# beerSch00.net
KiCad netlist of a schematic drawn in EAGLE
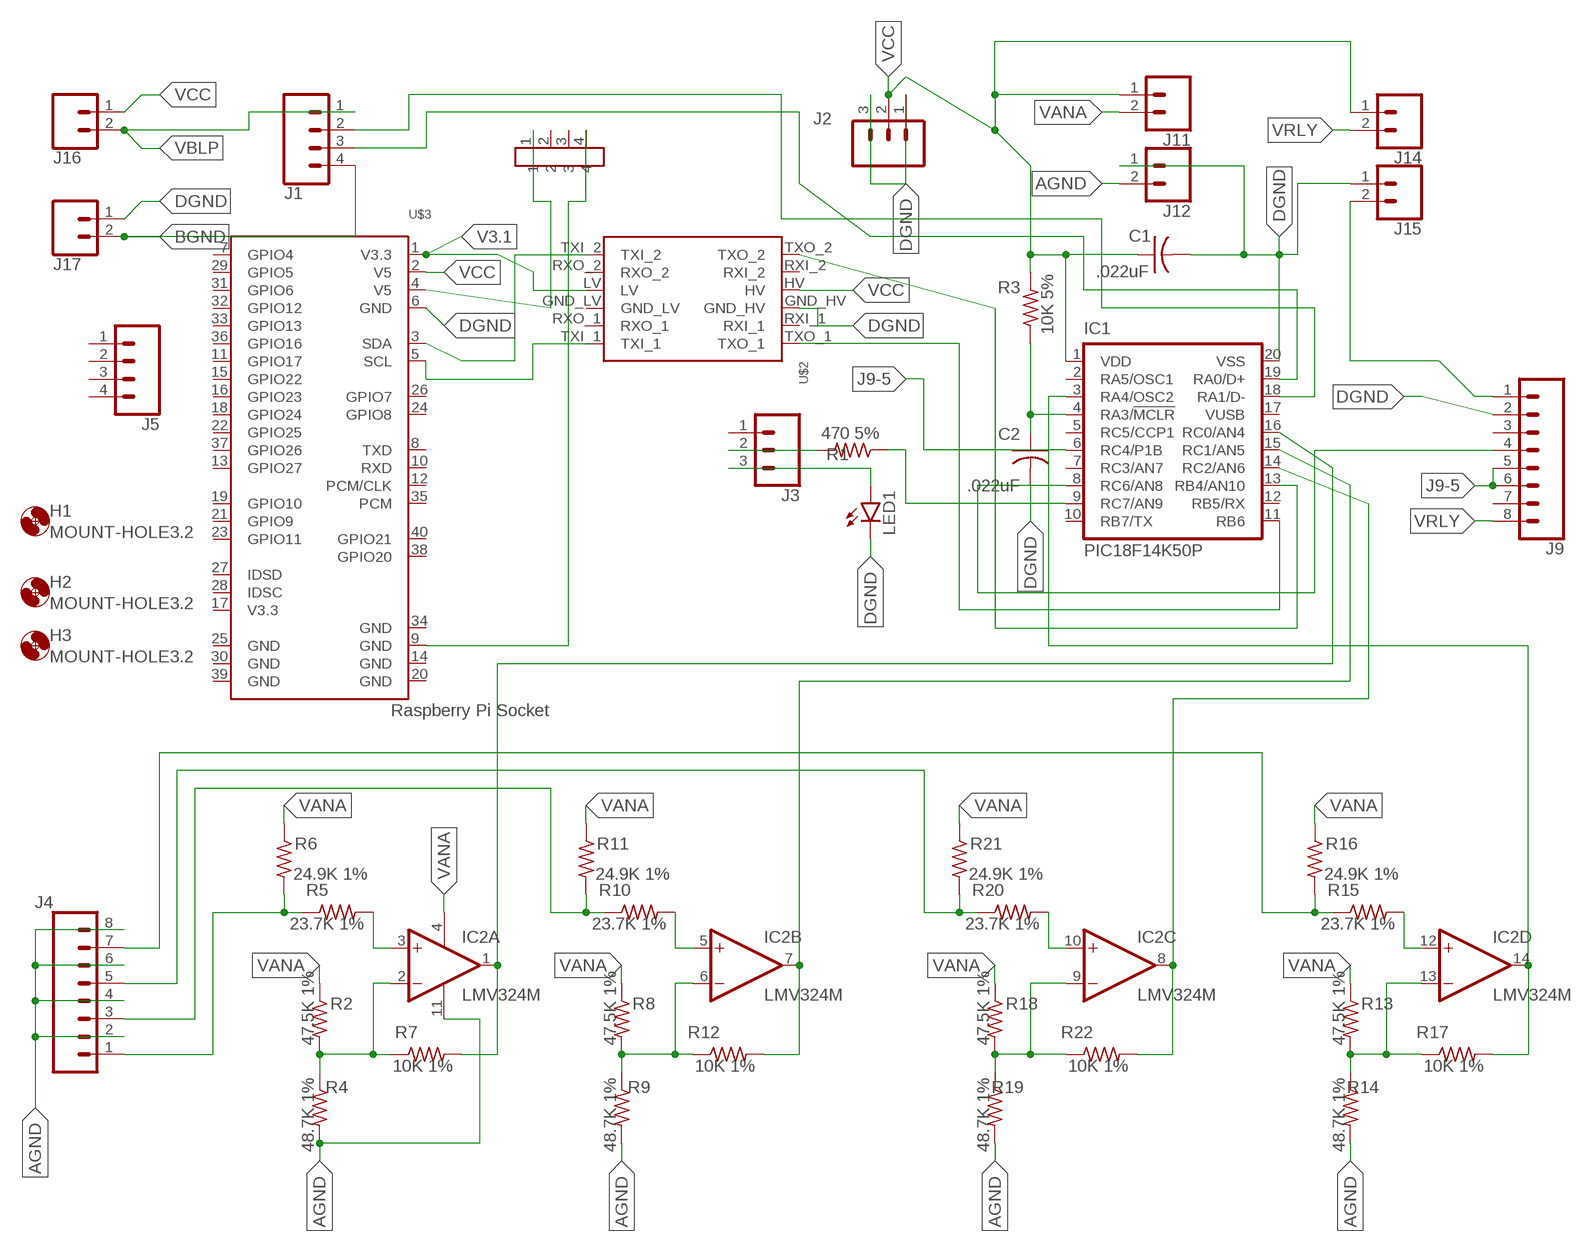
[diagram p0: schematic, sheet 1]

(export (version "E")
  (design (tool "Eeschema 10.0.6"))
  (components
    (comp (ref "C1")
      (value ".022uF")
      (footprint "eagle-import:C0805")
      (libsource (lib "eagle-import") (part "C-USC0805"))
    )
    (comp (ref "C2")
      (value ".022uF")
      (footprint "eagle-import:C0805")
      (libsource (lib "eagle-import") (part "C-USC0805"))
    )
    (comp (ref "H1")
      (value "MOUNT-HOLE3.2")
      (footprint "eagle-import:3,2")
      (libsource (lib "eagle-import") (part "MOUNT-HOLE3.2"))
    )
    (comp (ref "H2")
      (value "MOUNT-HOLE3.2")
      (footprint "eagle-import:3,2")
      (libsource (lib "eagle-import") (part "MOUNT-HOLE3.2"))
    )
    (comp (ref "H3")
      (value "MOUNT-HOLE3.2")
      (footprint "eagle-import:3,2")
      (libsource (lib "eagle-import") (part "MOUNT-HOLE3.2"))
    )
    (comp (ref "IC1")
      (value "PIC18F14K50P")
      (footprint "eagle-import:DIL20")
      (libsource (lib "eagle-import") (part "PIC18F14K50P"))
    )
    (comp (ref "IC2")
      (value "LMV324M")
      (footprint "eagle-import:SO14")
      (libsource (lib "eagle-import") (part "LMV324?M"))
    )
    (comp (ref "J1")
      (value "CONN_04")
      (footprint "eagle-import:1X04")
      (libsource (lib "eagle-import") (part "CONN_04"))
    )
    (comp (ref "J2")
      (value "CONN_03")
      (footprint "eagle-import:1X03")
      (libsource (lib "eagle-import") (part "CONN_03"))
    )
    (comp (ref "J3")
      (value "CONN_03")
      (footprint "eagle-import:1X03")
      (libsource (lib "eagle-import") (part "CONN_03"))
    )
    (comp (ref "J4")
      (value "CONN_08\"")
      (footprint "eagle-import:1X08")
      (libsource (lib "eagle-import") (part "CONN_08{dblquote}"))
    )
    (comp (ref "J5")
      (value "CONN_04")
      (footprint "eagle-import:1X04")
      (libsource (lib "eagle-import") (part "CONN_04"))
    )
    (comp (ref "J9")
      (value "CONN_08\"")
      (footprint "eagle-import:1X08")
      (libsource (lib "eagle-import") (part "CONN_08{dblquote}"))
    )
    (comp (ref "J11")
      (value "CONN_02")
      (footprint "eagle-import:1X02")
      (libsource (lib "eagle-import") (part "CONN_02"))
    )
    (comp (ref "J12")
      (value "CONN_02")
      (footprint "eagle-import:1X02")
      (libsource (lib "eagle-import") (part "CONN_02"))
    )
    (comp (ref "J14")
      (value "CONN_02")
      (footprint "eagle-import:1X02")
      (libsource (lib "eagle-import") (part "CONN_02"))
    )
    (comp (ref "J15")
      (value "CONN_02")
      (footprint "eagle-import:1X02")
      (libsource (lib "eagle-import") (part "CONN_02"))
    )
    (comp (ref "J16")
      (value "CONN_02")
      (footprint "eagle-import:1X02")
      (libsource (lib "eagle-import") (part "CONN_02"))
    )
    (comp (ref "J17")
      (value "CONN_02")
      (footprint "eagle-import:1X02")
      (libsource (lib "eagle-import") (part "CONN_02"))
    )
    (comp (ref "LED1")
      (value "LEDSML0805")
      (footprint "eagle-import:SML0805")
      (libsource (lib "eagle-import") (part "LEDSML0805"))
    )
    (comp (ref "R1")
      (value "470 5%")
      (footprint "eagle-import:R0603")
      (libsource (lib "eagle-import") (part "R-US_R0603"))
    )
    (comp (ref "R2")
      (value "47.5K 1%")
      (footprint "eagle-import:R0603")
      (libsource (lib "eagle-import") (part "R-US_R0603"))
    )
    (comp (ref "R3")
      (value "10K 5%")
      (footprint "eagle-import:R0603")
      (libsource (lib "eagle-import") (part "R-US_R0603"))
    )
    (comp (ref "R4")
      (value "48.7K 1%")
      (footprint "eagle-import:R0603")
      (libsource (lib "eagle-import") (part "R-US_R0603"))
    )
    (comp (ref "R5")
      (value "23.7K 1%")
      (footprint "eagle-import:R0603")
      (libsource (lib "eagle-import") (part "R-US_R0603"))
    )
    (comp (ref "R6")
      (value "24.9K 1%")
      (footprint "eagle-import:R0603")
      (libsource (lib "eagle-import") (part "R-US_R0603"))
    )
    (comp (ref "R7")
      (value "10K 1%")
      (footprint "eagle-import:R0603")
      (libsource (lib "eagle-import") (part "R-US_R0603"))
    )
    (comp (ref "R8")
      (value "47.5K 1%")
      (footprint "eagle-import:R0603")
      (libsource (lib "eagle-import") (part "R-US_R0603"))
    )
    (comp (ref "R9")
      (value "48.7K 1%")
      (footprint "eagle-import:R0603")
      (libsource (lib "eagle-import") (part "R-US_R0603"))
    )
    (comp (ref "R10")
      (value "23.7K 1%")
      (footprint "eagle-import:R0603")
      (libsource (lib "eagle-import") (part "R-US_R0603"))
    )
    (comp (ref "R11")
      (value "24.9K 1%")
      (footprint "eagle-import:R0603")
      (libsource (lib "eagle-import") (part "R-US_R0603"))
    )
    (comp (ref "R12")
      (value "10K 1%")
      (footprint "eagle-import:R0603")
      (libsource (lib "eagle-import") (part "R-US_R0603"))
    )
    (comp (ref "R13")
      (value "47.5K 1%")
      (footprint "eagle-import:R0603")
      (libsource (lib "eagle-import") (part "R-US_R0603"))
    )
    (comp (ref "R14")
      (value "48.7K 1%")
      (footprint "eagle-import:R0603")
      (libsource (lib "eagle-import") (part "R-US_R0603"))
    )
    (comp (ref "R15")
      (value "23.7K 1%")
      (footprint "eagle-import:R0603")
      (libsource (lib "eagle-import") (part "R-US_R0603"))
    )
    (comp (ref "R16")
      (value "24.9K 1%")
      (footprint "eagle-import:R0603")
      (libsource (lib "eagle-import") (part "R-US_R0603"))
    )
    (comp (ref "R17")
      (value "10K 1%")
      (footprint "eagle-import:R0603")
      (libsource (lib "eagle-import") (part "R-US_R0603"))
    )
    (comp (ref "R18")
      (value "47.5K 1%")
      (footprint "eagle-import:R0603")
      (libsource (lib "eagle-import") (part "R-US_R0603"))
    )
    (comp (ref "R19")
      (value "48.7K 1%")
      (footprint "eagle-import:R0603")
      (libsource (lib "eagle-import") (part "R-US_R0603"))
    )
    (comp (ref "R20")
      (value "23.7K 1%")
      (footprint "eagle-import:R0603")
      (libsource (lib "eagle-import") (part "R-US_R0603"))
    )
    (comp (ref "R21")
      (value "24.9K 1%")
      (footprint "eagle-import:R0603")
      (libsource (lib "eagle-import") (part "R-US_R0603"))
    )
    (comp (ref "R22")
      (value "10K 1%")
      (footprint "eagle-import:R0603")
      (libsource (lib "eagle-import") (part "R-US_R0603"))
    )
    (comp (ref "U$1")
      (value "CONN_4")
      (footprint "eagle-import:PINS_90")
      (libsource (lib "eagle-import") (part "CONN_4"))
    )
    (comp (ref "U$2")
      (value "LEVELCONV")
      (footprint "eagle-import:PLUG_THROUGHHOLE")
      (libsource (lib "eagle-import") (part "LEVELCONV"))
    )
    (comp (ref "U$3")
      (value "RASPBERRYPI_SOCKET_UNDER")
      (footprint "eagle-import:RASPBERRYPI_UNDERBD")
      (libsource (lib "eagle-import") (part "RASPBERRYPI_SOCKET_UNDER"))
    )
  )
  (nets
    (net (code "1") (name "AGND") (class "Default")
      (node (ref "IC2") (pin "11") (pinfunction "V-_11") (pintype "power_in"))
      (node (ref "J12") (pin "2") (pinfunction "2_2") (pintype "passive"))
      (node (ref "J4") (pin "2") (pinfunction "2_2") (pintype "passive"))
      (node (ref "J4") (pin "4") (pinfunction "4_4") (pintype "passive"))
      (node (ref "J4") (pin "6") (pinfunction "6_6") (pintype "passive"))
      (node (ref "J4") (pin "8") (pinfunction "8_8") (pintype "passive"))
      (node (ref "R14") (pin "2") (pinfunction "2_2") (pintype "passive"))
      (node (ref "R19") (pin "2") (pinfunction "2_2") (pintype "passive"))
      (node (ref "R4") (pin "2") (pinfunction "2_2") (pintype "passive"))
      (node (ref "R9") (pin "2") (pinfunction "2_2") (pintype "passive"))
    )
    (net (code "2") (name "BGND") (class "Default")
      (node (ref "J1") (pin "4") (pinfunction "4_4") (pintype "passive"))
      (node (ref "J17") (pin "2") (pinfunction "2_2") (pintype "passive"))
    )
    (net (code "3") (name "DGND") (class "Default")
      (node (ref "C1") (pin "2") (pinfunction "2_2") (pintype "passive"))
      (node (ref "C2") (pin "2") (pinfunction "2_2") (pintype "passive"))
      (node (ref "IC1") (pin "20") (pinfunction "VSS_20") (pintype "power_in"))
      (node (ref "J12") (pin "1") (pinfunction "1_1") (pintype "passive"))
      (node (ref "J15") (pin "1") (pinfunction "1_1") (pintype "passive"))
      (node (ref "J17") (pin "1") (pinfunction "1_1") (pintype "passive"))
      (node (ref "J2") (pin "1") (pinfunction "1_1") (pintype "passive"))
      (node (ref "J2") (pin "3") (pinfunction "3_3") (pintype "passive"))
      (node (ref "J9") (pin "2") (pinfunction "2_2") (pintype "passive"))
      (node (ref "LED1") (pin "C") (pinfunction "C_C") (pintype "passive"))
      (node (ref "U$2") (pin "GND_HV") (pinfunction "GND_HV_GND_HV") (pintype "bidirectional"))
      (node (ref "U$3") (pin "6") (pinfunction "GND_6") (pintype "bidirectional"))
    )
    (net (code "4") (name "J9-5") (class "Default")
      (node (ref "IC1") (pin "6") (pinfunction "RC4/P1B_6") (pintype "bidirectional"))
      (node (ref "J9") (pin "5") (pinfunction "5_5") (pintype "passive"))
      (node (ref "J9") (pin "6") (pinfunction "6_6") (pintype "passive"))
    )
    (net (code "5") (name "Net-(IC1-RA0{slash}D+)") (class "Default")
      (node (ref "IC1") (pin "19") (pinfunction "RA0/D+_19") (pintype "bidirectional"))
      (node (ref "J1") (pin "3") (pinfunction "3_3") (pintype "passive"))
    )
    (net (code "6") (name "Net-(IC1-RA1{slash}D-)") (class "Default")
      (node (ref "IC1") (pin "18") (pinfunction "RA1/D-_18") (pintype "bidirectional"))
      (node (ref "J1") (pin "2") (pinfunction "2_2") (pintype "passive"))
    )
    (net (code "7") (name "Net-(IC1-RA3{slash}~{MCLR})") (class "Default")
      (node (ref "C2") (pin "1") (pinfunction "1_1") (pintype "passive"))
      (node (ref "IC1") (pin "4") (pinfunction "RA3/~{MCLR}_4") (pintype "bidirectional"))
      (node (ref "R3") (pin "1") (pinfunction "1_1") (pintype "passive"))
    )
    (net (code "8") (name "Net-(IC1-RA4{slash}OSC2)") (class "Default")
      (node (ref "IC1") (pin "3") (pinfunction "RA4/OSC2_3") (pintype "bidirectional"))
      (node (ref "IC2") (pin "14") (pinfunction "OUT_14") (pintype "output"))
      (node (ref "R17") (pin "2") (pinfunction "2_2") (pintype "passive"))
    )
    (net (code "9") (name "Net-(IC1-RB4{slash}AN10)") (class "Default")
      (node (ref "IC1") (pin "13") (pinfunction "RB4/AN10_13") (pintype "bidirectional"))
      (node (ref "U$2") (pin "TXO_2") (pinfunction "TXO_2_TXO_2") (pintype "bidirectional"))
    )
    (net (code "10") (name "Net-(IC1-RB6)") (class "Default")
      (node (ref "IC1") (pin "11") (pinfunction "RB6_11") (pintype "bidirectional"))
      (node (ref "U$2") (pin "TXO_1") (pinfunction "TXO_1_TXO_1") (pintype "bidirectional"))
    )
    (net (code "11") (name "Net-(IC1-RC0{slash}AN4)") (class "Default")
      (node (ref "IC1") (pin "16") (pinfunction "RC0/AN4_16") (pintype "bidirectional"))
      (node (ref "IC2") (pin "1") (pinfunction "OUT_1") (pintype "output"))
      (node (ref "R7") (pin "2") (pinfunction "2_2") (pintype "passive"))
    )
    (net (code "12") (name "Net-(IC1-RC1{slash}AN5)") (class "Default")
      (node (ref "IC1") (pin "15") (pinfunction "RC1/AN5_15") (pintype "bidirectional"))
      (node (ref "IC2") (pin "7") (pinfunction "OUT_7") (pintype "output"))
      (node (ref "R12") (pin "2") (pinfunction "2_2") (pintype "passive"))
    )
    (net (code "13") (name "Net-(IC1-RC2{slash}AN6)") (class "Default")
      (node (ref "IC1") (pin "14") (pinfunction "RC2/AN6_14") (pintype "bidirectional"))
      (node (ref "IC2") (pin "8") (pinfunction "OUT_8") (pintype "output"))
      (node (ref "R22") (pin "2") (pinfunction "2_2") (pintype "passive"))
    )
    (net (code "14") (name "Net-(IC1-RC6{slash}AN8)") (class "Default")
      (node (ref "IC1") (pin "8") (pinfunction "RC6/AN8_8") (pintype "bidirectional"))
      (node (ref "J9") (pin "4") (pinfunction "4_4") (pintype "passive"))
    )
    (net (code "15") (name "Net-(IC1-RC7{slash}AN9)") (class "Default")
      (node (ref "IC1") (pin "9") (pinfunction "RC7/AN9_9") (pintype "bidirectional"))
      (node (ref "R1") (pin "1") (pinfunction "1_1") (pintype "passive"))
    )
    (net (code "16") (name "Net-(IC2A-+IN)") (class "Default")
      (node (ref "IC2") (pin "3") (pinfunction "+IN_3") (pintype "input"))
      (node (ref "R5") (pin "2") (pinfunction "2_2") (pintype "passive"))
    )
    (net (code "17") (name "Net-(IC2A--IN)") (class "Default")
      (node (ref "IC2") (pin "2") (pinfunction "-IN_2") (pintype "input"))
      (node (ref "R2") (pin "2") (pinfunction "2_2") (pintype "passive"))
      (node (ref "R4") (pin "1") (pinfunction "1_1") (pintype "passive"))
      (node (ref "R7") (pin "1") (pinfunction "1_1") (pintype "passive"))
    )
    (net (code "18") (name "Net-(IC2B-+IN)") (class "Default")
      (node (ref "IC2") (pin "5") (pinfunction "+IN_5") (pintype "input"))
      (node (ref "R10") (pin "2") (pinfunction "2_2") (pintype "passive"))
    )
    (net (code "19") (name "Net-(IC2B--IN)") (class "Default")
      (node (ref "IC2") (pin "6") (pinfunction "-IN_6") (pintype "input"))
      (node (ref "R12") (pin "1") (pinfunction "1_1") (pintype "passive"))
      (node (ref "R8") (pin "2") (pinfunction "2_2") (pintype "passive"))
      (node (ref "R9") (pin "1") (pinfunction "1_1") (pintype "passive"))
    )
    (net (code "20") (name "Net-(IC2C-+IN)") (class "Default")
      (node (ref "IC2") (pin "10") (pinfunction "+IN_10") (pintype "input"))
      (node (ref "R20") (pin "2") (pinfunction "2_2") (pintype "passive"))
    )
    (net (code "21") (name "Net-(IC2C--IN)") (class "Default")
      (node (ref "IC2") (pin "9") (pinfunction "-IN_9") (pintype "input"))
      (node (ref "R18") (pin "2") (pinfunction "2_2") (pintype "passive"))
      (node (ref "R19") (pin "1") (pinfunction "1_1") (pintype "passive"))
      (node (ref "R22") (pin "1") (pinfunction "1_1") (pintype "passive"))
    )
    (net (code "22") (name "Net-(IC2D-+IN)") (class "Default")
      (node (ref "IC2") (pin "12") (pinfunction "+IN_12") (pintype "input"))
      (node (ref "R15") (pin "2") (pinfunction "2_2") (pintype "passive"))
    )
    (net (code "23") (name "Net-(IC2D--IN)") (class "Default")
      (node (ref "IC2") (pin "13") (pinfunction "-IN_13") (pintype "input"))
      (node (ref "R13") (pin "2") (pinfunction "2_2") (pintype "passive"))
      (node (ref "R14") (pin "1") (pinfunction "1_1") (pintype "passive"))
      (node (ref "R17") (pin "1") (pinfunction "1_1") (pintype "passive"))
    )
    (net (code "24") (name "Net-(J3-Pad2)") (class "Default")
      (node (ref "J3") (pin "2") (pinfunction "2_2") (pintype "passive"))
      (node (ref "R1") (pin "2") (pinfunction "2_2") (pintype "passive"))
    )
    (net (code "25") (name "Net-(J3-Pad3)") (class "Default")
      (node (ref "J3") (pin "3") (pinfunction "3_3") (pintype "passive"))
      (node (ref "LED1") (pin "A") (pinfunction "A_A") (pintype "passive"))
    )
    (net (code "26") (name "Net-(J4-Pad1)") (class "Default")
      (node (ref "J4") (pin "1") (pinfunction "1_1") (pintype "passive"))
      (node (ref "R5") (pin "1") (pinfunction "1_1") (pintype "passive"))
      (node (ref "R6") (pin "2") (pinfunction "2_2") (pintype "passive"))
    )
    (net (code "27") (name "Net-(J4-Pad3)") (class "Default")
      (node (ref "J4") (pin "3") (pinfunction "3_3") (pintype "passive"))
      (node (ref "R10") (pin "1") (pinfunction "1_1") (pintype "passive"))
      (node (ref "R11") (pin "2") (pinfunction "2_2") (pintype "passive"))
    )
    (net (code "28") (name "Net-(J4-Pad5)") (class "Default")
      (node (ref "J4") (pin "5") (pinfunction "5_5") (pintype "passive"))
      (node (ref "R20") (pin "1") (pinfunction "1_1") (pintype "passive"))
      (node (ref "R21") (pin "2") (pinfunction "2_2") (pintype "passive"))
    )
    (net (code "29") (name "Net-(J4-Pad7)") (class "Default")
      (node (ref "J4") (pin "7") (pinfunction "7_7") (pintype "passive"))
      (node (ref "R15") (pin "1") (pinfunction "1_1") (pintype "passive"))
      (node (ref "R16") (pin "2") (pinfunction "2_2") (pintype "passive"))
    )
    (net (code "30") (name "Net-(J15-Pad2)") (class "Default")
      (node (ref "J15") (pin "2") (pinfunction "2_2") (pintype "passive"))
      (node (ref "J9") (pin "1") (pinfunction "1_1") (pintype "passive"))
    )
    (net (code "31") (name "Net-(U$1-Pad1)") (class "Default")
      (node (ref "U$1") (pin "1") (pinfunction "1_1") (pintype "bidirectional"))
      (node (ref "U$3") (pin "4") (pinfunction "V5_4") (pintype "bidirectional"))
    )
    (net (code "32") (name "Net-(U$1-Pad4)") (class "Default")
      (node (ref "U$1") (pin "4") (pinfunction "4_4") (pintype "bidirectional"))
      (node (ref "U$3") (pin "9") (pinfunction "GND_9") (pintype "bidirectional"))
    )
    (net (code "33") (name "Net-(U$3-SCL)") (class "Default")
      (node (ref "U$2") (pin "TXI_1") (pinfunction "TXI_1_TXI_1") (pintype "bidirectional"))
      (node (ref "U$3") (pin "5") (pinfunction "SCL_5") (pintype "bidirectional"))
    )
    (net (code "34") (name "Net-(U$3-SDA)") (class "Default")
      (node (ref "U$2") (pin "TXI_2") (pinfunction "TXI_2_TXI_2") (pintype "bidirectional"))
      (node (ref "U$3") (pin "3") (pinfunction "SDA_3") (pintype "bidirectional"))
    )
    (net (code "35") (name "V3.1") (class "Default")
      (node (ref "U$2") (pin "LV") (pinfunction "LV_LV") (pintype "bidirectional"))
      (node (ref "U$3") (pin "1") (pinfunction "V3.3_1") (pintype "bidirectional"))
    )
    (net (code "36") (name "VANA") (class "Default")
      (node (ref "IC2") (pin "4") (pinfunction "V+_4") (pintype "power_in"))
      (node (ref "J11") (pin "2") (pinfunction "2_2") (pintype "passive"))
      (node (ref "R11") (pin "1") (pinfunction "1_1") (pintype "passive"))
      (node (ref "R13") (pin "1") (pinfunction "1_1") (pintype "passive"))
      (node (ref "R16") (pin "1") (pinfunction "1_1") (pintype "passive"))
      (node (ref "R18") (pin "1") (pinfunction "1_1") (pintype "passive"))
      (node (ref "R2") (pin "1") (pinfunction "1_1") (pintype "passive"))
      (node (ref "R21") (pin "1") (pinfunction "1_1") (pintype "passive"))
      (node (ref "R6") (pin "1") (pinfunction "1_1") (pintype "passive"))
      (node (ref "R8") (pin "1") (pinfunction "1_1") (pintype "passive"))
    )
    (net (code "37") (name "VBLP") (class "Default")
      (node (ref "J1") (pin "1") (pinfunction "1_1") (pintype "passive"))
      (node (ref "J16") (pin "2") (pinfunction "2_2") (pintype "passive"))
    )
    (net (code "38") (name "VCC") (class "Default")
      (node (ref "C1") (pin "1") (pinfunction "1_1") (pintype "passive"))
      (node (ref "IC1") (pin "1") (pinfunction "VDD_1") (pintype "power_in"))
      (node (ref "J11") (pin "1") (pinfunction "1_1") (pintype "passive"))
      (node (ref "J14") (pin "1") (pinfunction "1_1") (pintype "passive"))
      (node (ref "J16") (pin "1") (pinfunction "1_1") (pintype "passive"))
      (node (ref "J2") (pin "2") (pinfunction "2_2") (pintype "passive"))
      (node (ref "R3") (pin "2") (pinfunction "2_2") (pintype "passive"))
      (node (ref "U$2") (pin "HV") (pinfunction "HV_HV") (pintype "bidirectional"))
      (node (ref "U$3") (pin "2") (pinfunction "V5_2") (pintype "bidirectional"))
    )
    (net (code "39") (name "VRLY") (class "Default")
      (node (ref "J14") (pin "2") (pinfunction "2_2") (pintype "passive"))
      (node (ref "J9") (pin "8") (pinfunction "8_8") (pintype "passive"))
    )
    (net (code "40") (name "unconnected-(IC1-RA5{slash}OSC1-Pad2)") (class "Default")
      (node (ref "IC1") (pin "2") (pinfunction "RA5/OSC1_2") (pintype "bidirectional"))
    )
    (net (code "41") (name "unconnected-(IC1-RB5{slash}RX-Pad12)") (class "Default")
      (node (ref "IC1") (pin "12") (pinfunction "RB5/RX_12") (pintype "bidirectional"))
    )
    (net (code "42") (name "unconnected-(IC1-RB7{slash}TX-Pad10)") (class "Default")
      (node (ref "IC1") (pin "10") (pinfunction "RB7/TX_10") (pintype "bidirectional"))
    )
    (net (code "43") (name "unconnected-(IC1-RC3{slash}AN7-Pad7)") (class "Default")
      (node (ref "IC1") (pin "7") (pinfunction "RC3/AN7_7") (pintype "bidirectional"))
    )
    (net (code "44") (name "unconnected-(IC1-RC5{slash}CCP1-Pad5)") (class "Default")
      (node (ref "IC1") (pin "5") (pinfunction "RC5/CCP1_5") (pintype "bidirectional"))
    )
    (net (code "45") (name "unconnected-(IC1-VUSB-Pad17)") (class "Default")
      (node (ref "IC1") (pin "17") (pinfunction "VUSB_17") (pintype "bidirectional"))
    )
    (net (code "46") (name "unconnected-(J3-Pad1)") (class "Default")
      (node (ref "J3") (pin "1") (pinfunction "1_1") (pintype "passive"))
    )
    (net (code "47") (name "unconnected-(J5-Pad1)") (class "Default")
      (node (ref "J5") (pin "1") (pinfunction "1_1") (pintype "passive"))
    )
    (net (code "48") (name "unconnected-(J5-Pad2)") (class "Default")
      (node (ref "J5") (pin "2") (pinfunction "2_2") (pintype "passive"))
    )
    (net (code "49") (name "unconnected-(J5-Pad3)") (class "Default")
      (node (ref "J5") (pin "3") (pinfunction "3_3") (pintype "passive"))
    )
    (net (code "50") (name "unconnected-(J5-Pad4)") (class "Default")
      (node (ref "J5") (pin "4") (pinfunction "4_4") (pintype "passive"))
    )
    (net (code "51") (name "unconnected-(J9-Pad3)") (class "Default")
      (node (ref "J9") (pin "3") (pinfunction "3_3") (pintype "passive"))
    )
    (net (code "52") (name "unconnected-(J9-Pad7)") (class "Default")
      (node (ref "J9") (pin "7") (pinfunction "7_7") (pintype "passive"))
    )
    (net (code "53") (name "unconnected-(U$1-Pad2)") (class "Default")
      (node (ref "U$1") (pin "2") (pinfunction "2_2") (pintype "bidirectional"))
    )
    (net (code "54") (name "unconnected-(U$1-Pad3)") (class "Default")
      (node (ref "U$1") (pin "3") (pinfunction "3_3") (pintype "bidirectional"))
    )
    (net (code "55") (name "unconnected-(U$2-PadGND_LV)") (class "Default")
      (node (ref "U$2") (pin "GND_LV") (pinfunction "GND_LV_GND_LV") (pintype "bidirectional"))
    )
    (net (code "56") (name "unconnected-(U$2-PadRXI_1)") (class "Default")
      (node (ref "U$2") (pin "RXI_1") (pinfunction "RXI_1_RXI_1") (pintype "bidirectional"))
    )
    (net (code "57") (name "unconnected-(U$2-PadRXI_2)") (class "Default")
      (node (ref "U$2") (pin "RXI_2") (pinfunction "RXI_2_RXI_2") (pintype "bidirectional"))
    )
    (net (code "58") (name "unconnected-(U$2-PadRXO_1)") (class "Default")
      (node (ref "U$2") (pin "RXO_1") (pinfunction "RXO_1_RXO_1") (pintype "bidirectional"))
    )
    (net (code "59") (name "unconnected-(U$2-PadRXO_2)") (class "Default")
      (node (ref "U$2") (pin "RXO_2") (pinfunction "RXO_2_RXO_2") (pintype "bidirectional"))
    )
    (net (code "60") (name "unconnected-(U$3-GND-Pad14)") (class "Default")
      (node (ref "U$3") (pin "14") (pinfunction "GND_14") (pintype "bidirectional"))
    )
    (net (code "61") (name "unconnected-(U$3-GND-Pad20)") (class "Default")
      (node (ref "U$3") (pin "20") (pinfunction "GND_20") (pintype "bidirectional"))
    )
    (net (code "62") (name "unconnected-(U$3-GND-Pad25)") (class "Default")
      (node (ref "U$3") (pin "25") (pinfunction "GND_25") (pintype "bidirectional"))
    )
    (net (code "63") (name "unconnected-(U$3-GND-Pad30)") (class "Default")
      (node (ref "U$3") (pin "30") (pinfunction "GND_30") (pintype "bidirectional"))
    )
    (net (code "64") (name "unconnected-(U$3-GND-Pad34)") (class "Default")
      (node (ref "U$3") (pin "34") (pinfunction "GND_34") (pintype "bidirectional"))
    )
    (net (code "65") (name "unconnected-(U$3-GND-Pad39)") (class "Default")
      (node (ref "U$3") (pin "39") (pinfunction "GND_39") (pintype "bidirectional"))
    )
    (net (code "66") (name "unconnected-(U$3-GPIO4-Pad7)") (class "Default")
      (node (ref "U$3") (pin "7") (pinfunction "GPIO4_7") (pintype "bidirectional"))
    )
    (net (code "67") (name "unconnected-(U$3-GPIO5-Pad29)") (class "Default")
      (node (ref "U$3") (pin "29") (pinfunction "GPIO5_29") (pintype "bidirectional"))
    )
    (net (code "68") (name "unconnected-(U$3-GPIO6-Pad31)") (class "Default")
      (node (ref "U$3") (pin "31") (pinfunction "GPIO6_31") (pintype "bidirectional"))
    )
    (net (code "69") (name "unconnected-(U$3-GPIO7-Pad26)") (class "Default")
      (node (ref "U$3") (pin "26") (pinfunction "GPIO7_26") (pintype "bidirectional"))
    )
    (net (code "70") (name "unconnected-(U$3-GPIO8-Pad24)") (class "Default")
      (node (ref "U$3") (pin "24") (pinfunction "GPIO8_24") (pintype "bidirectional"))
    )
    (net (code "71") (name "unconnected-(U$3-GPIO9-Pad21)") (class "Default")
      (node (ref "U$3") (pin "21") (pinfunction "GPIO9_21") (pintype "bidirectional"))
    )
    (net (code "72") (name "unconnected-(U$3-GPIO10-Pad19)") (class "Default")
      (node (ref "U$3") (pin "19") (pinfunction "GPIO10_19") (pintype "bidirectional"))
    )
    (net (code "73") (name "unconnected-(U$3-GPIO11-Pad23)") (class "Default")
      (node (ref "U$3") (pin "23") (pinfunction "GPIO11_23") (pintype "bidirectional"))
    )
    (net (code "74") (name "unconnected-(U$3-GPIO12-Pad32)") (class "Default")
      (node (ref "U$3") (pin "32") (pinfunction "GPIO12_32") (pintype "bidirectional"))
    )
    (net (code "75") (name "unconnected-(U$3-GPIO13-Pad33)") (class "Default")
      (node (ref "U$3") (pin "33") (pinfunction "GPIO13_33") (pintype "bidirectional"))
    )
    (net (code "76") (name "unconnected-(U$3-GPIO16-Pad36)") (class "Default")
      (node (ref "U$3") (pin "36") (pinfunction "GPIO16_36") (pintype "bidirectional"))
    )
    (net (code "77") (name "unconnected-(U$3-GPIO17-Pad11)") (class "Default")
      (node (ref "U$3") (pin "11") (pinfunction "GPIO17_11") (pintype "bidirectional"))
    )
    (net (code "78") (name "unconnected-(U$3-GPIO20-Pad38)") (class "Default")
      (node (ref "U$3") (pin "38") (pinfunction "GPIO20_38") (pintype "bidirectional"))
    )
    (net (code "79") (name "unconnected-(U$3-GPIO21-Pad40)") (class "Default")
      (node (ref "U$3") (pin "40") (pinfunction "GPIO21_40") (pintype "bidirectional"))
    )
    (net (code "80") (name "unconnected-(U$3-GPIO22-Pad15)") (class "Default")
      (node (ref "U$3") (pin "15") (pinfunction "GPIO22_15") (pintype "bidirectional"))
    )
    (net (code "81") (name "unconnected-(U$3-GPIO23-Pad16)") (class "Default")
      (node (ref "U$3") (pin "16") (pinfunction "GPIO23_16") (pintype "bidirectional"))
    )
    (net (code "82") (name "unconnected-(U$3-GPIO24-Pad18)") (class "Default")
      (node (ref "U$3") (pin "18") (pinfunction "GPIO24_18") (pintype "bidirectional"))
    )
    (net (code "83") (name "unconnected-(U$3-GPIO25-Pad22)") (class "Default")
      (node (ref "U$3") (pin "22") (pinfunction "GPIO25_22") (pintype "bidirectional"))
    )
    (net (code "84") (name "unconnected-(U$3-GPIO26-Pad37)") (class "Default")
      (node (ref "U$3") (pin "37") (pinfunction "GPIO26_37") (pintype "bidirectional"))
    )
    (net (code "85") (name "unconnected-(U$3-GPIO27-Pad13)") (class "Default")
      (node (ref "U$3") (pin "13") (pinfunction "GPIO27_13") (pintype "bidirectional"))
    )
    (net (code "86") (name "unconnected-(U$3-IDSC-Pad28)") (class "Default")
      (node (ref "U$3") (pin "28") (pinfunction "IDSC_28") (pintype "bidirectional"))
    )
    (net (code "87") (name "unconnected-(U$3-IDSD-Pad27)") (class "Default")
      (node (ref "U$3") (pin "27") (pinfunction "IDSD_27") (pintype "bidirectional"))
    )
    (net (code "88") (name "unconnected-(U$3-PCM-Pad35)") (class "Default")
      (node (ref "U$3") (pin "35") (pinfunction "PCM_35") (pintype "bidirectional"))
    )
    (net (code "89") (name "unconnected-(U$3-PCM{slash}CLK-Pad12)") (class "Default")
      (node (ref "U$3") (pin "12") (pinfunction "PCM/CLK_12") (pintype "bidirectional"))
    )
    (net (code "90") (name "unconnected-(U$3-RXD-Pad10)") (class "Default")
      (node (ref "U$3") (pin "10") (pinfunction "RXD_10") (pintype "bidirectional"))
    )
    (net (code "91") (name "unconnected-(U$3-TXD-Pad8)") (class "Default")
      (node (ref "U$3") (pin "8") (pinfunction "TXD_8") (pintype "bidirectional"))
    )
    (net (code "92") (name "unconnected-(U$3-V3.3-Pad17)") (class "Default")
      (node (ref "U$3") (pin "17") (pinfunction "V3.3_17") (pintype "bidirectional"))
    )
  )
)
